# schematic_v1.net
KiCad netlist of a schematic drawn in EAGLE
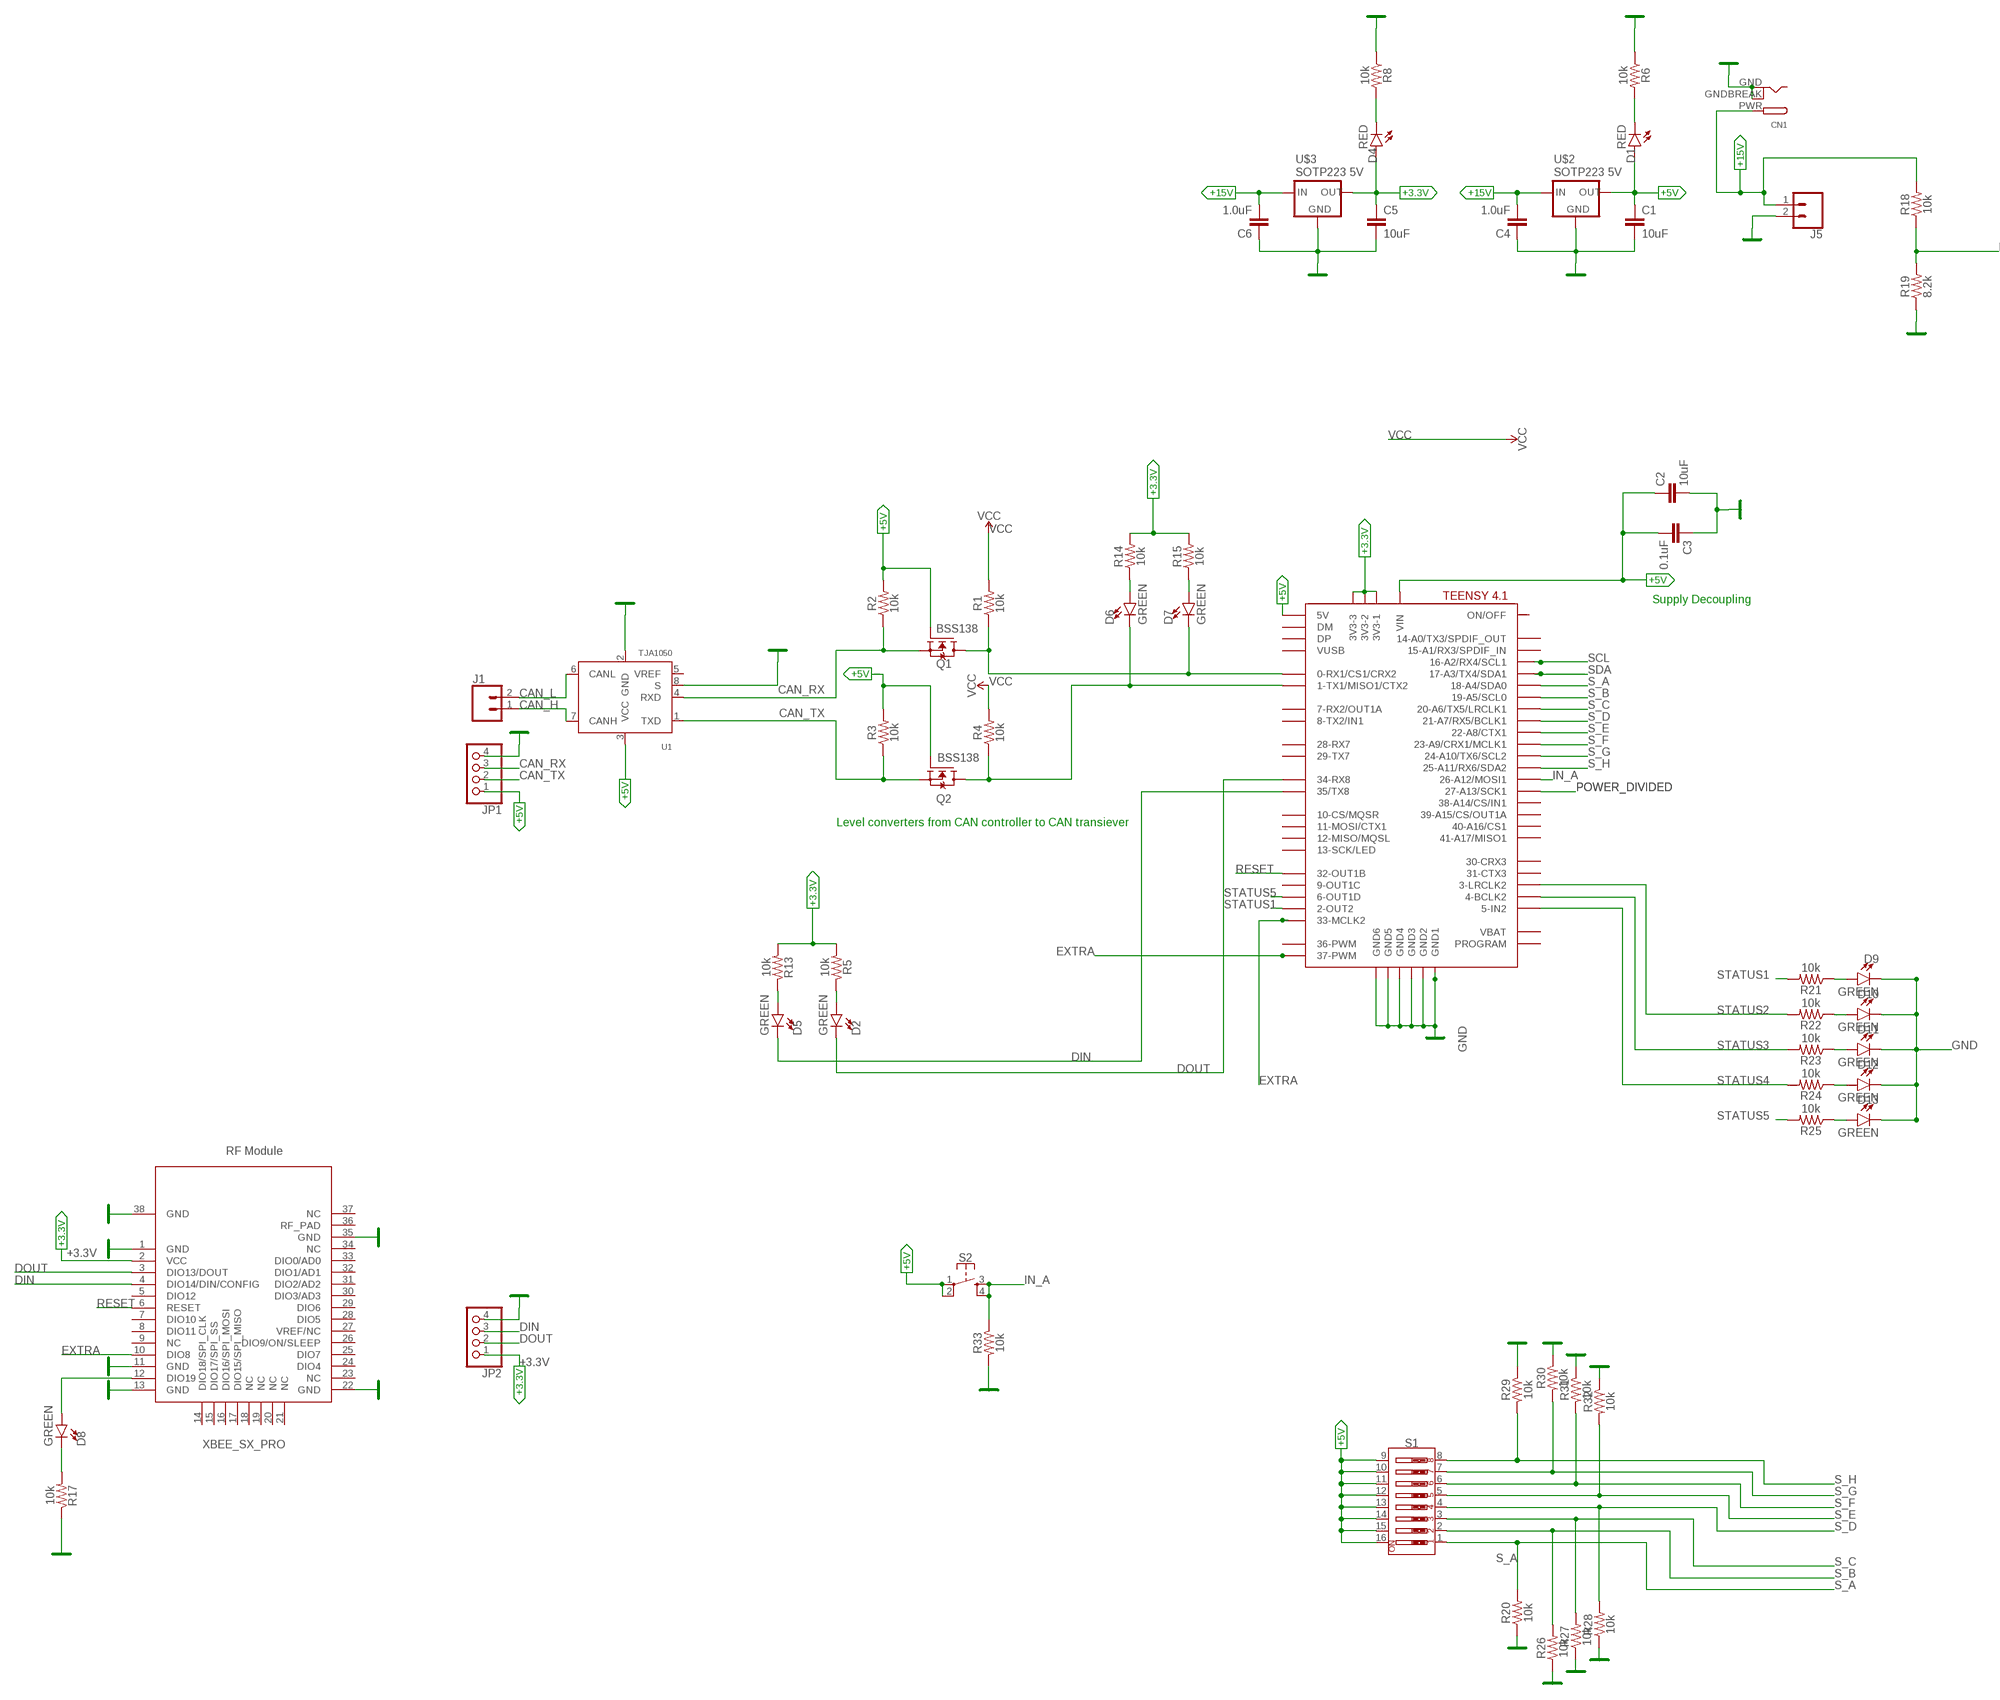
[diagram p0: schematic, sheet 1, part 1 of 2]
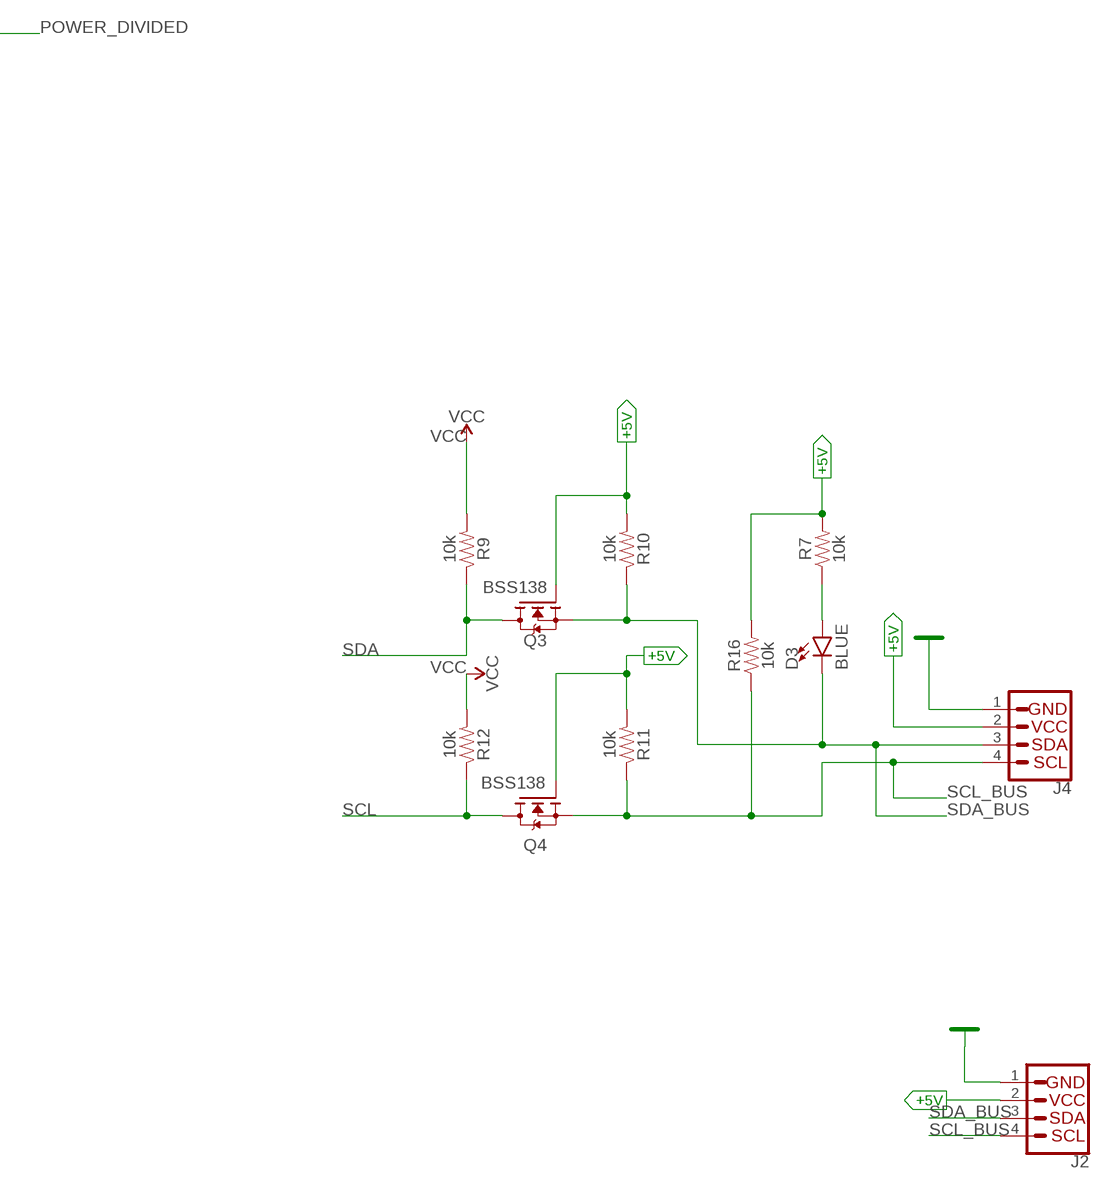
[diagram p1: schematic, sheet 1, part 2 of 2]

(export (version "E")
  (design (tool "Eeschema 10.0.6"))
  (components
    (comp (ref "C1")
      (value "10uF")
      (footprint "eagle-import:0603")
      (libsource (lib "eagle-import") (part "10UF-0603-6.3V-20%"))
    )
    (comp (ref "C2")
      (value "10uF")
      (footprint "eagle-import:0603")
      (libsource (lib "eagle-import") (part "10UF-0603-6.3V-20%"))
    )
    (comp (ref "C3")
      (value "0.1uF")
      (footprint "eagle-import:0603")
      (libsource (lib "eagle-import") (part "0.1UF-0603-25V-(+80/-20%)"))
    )
    (comp (ref "C4")
      (value "1.0uF")
      (footprint "eagle-import:0603")
      (libsource (lib "eagle-import") (part "1.0UF-0603-16V-10%"))
    )
    (comp (ref "C5")
      (value "10uF")
      (footprint "eagle-import:0603")
      (libsource (lib "eagle-import") (part "10UF-0603-6.3V-20%"))
    )
    (comp (ref "C6")
      (value "1.0uF")
      (footprint "eagle-import:0603")
      (libsource (lib "eagle-import") (part "1.0UF-0603-16V-10%"))
    )
    (comp (ref "CN1")
      (value "DCBARRELPTH")
      (footprint "eagle-import:DCJACK_2MM_PTH")
      (libsource (lib "eagle-import") (part "DCBARRELPTH"))
    )
    (comp (ref "D1")
      (value "RED")
      (footprint "eagle-import:LED-0603")
      (libsource (lib "eagle-import") (part "LED-RED0603"))
    )
    (comp (ref "D2")
      (value "GREEN")
      (footprint "eagle-import:LED-0603")
      (libsource (lib "eagle-import") (part "LED-GREEN0603"))
    )
    (comp (ref "D3")
      (value "BLUE")
      (footprint "eagle-import:LED-0603")
      (libsource (lib "eagle-import") (part "LED-BLUE0603"))
    )
    (comp (ref "D4")
      (value "RED")
      (footprint "eagle-import:LED-0603")
      (libsource (lib "eagle-import") (part "LED-RED0603"))
    )
    (comp (ref "D5")
      (value "GREEN")
      (footprint "eagle-import:LED-0603")
      (libsource (lib "eagle-import") (part "LED-GREEN0603"))
    )
    (comp (ref "D6")
      (value "GREEN")
      (footprint "eagle-import:LED-0603")
      (libsource (lib "eagle-import") (part "LED-GREEN0603"))
    )
    (comp (ref "D7")
      (value "GREEN")
      (footprint "eagle-import:LED-0603")
      (libsource (lib "eagle-import") (part "LED-GREEN0603"))
    )
    (comp (ref "D8")
      (value "GREEN")
      (footprint "eagle-import:LED-0603")
      (libsource (lib "eagle-import") (part "LED-GREEN0603"))
    )
    (comp (ref "D9")
      (value "GREEN")
      (footprint "eagle-import:LED-0603")
      (libsource (lib "eagle-import") (part "LED-GREEN0603"))
    )
    (comp (ref "D10")
      (value "GREEN")
      (footprint "eagle-import:LED-0603")
      (libsource (lib "eagle-import") (part "LED-GREEN0603"))
    )
    (comp (ref "D11")
      (value "GREEN")
      (footprint "eagle-import:LED-0603")
      (libsource (lib "eagle-import") (part "LED-GREEN0603"))
    )
    (comp (ref "D12")
      (value "GREEN")
      (footprint "eagle-import:LED-0603")
      (libsource (lib "eagle-import") (part "LED-GREEN0603"))
    )
    (comp (ref "D13")
      (value "GREEN")
      (footprint "eagle-import:LED-0603")
      (libsource (lib "eagle-import") (part "LED-GREEN0603"))
    )
    (comp (ref "J1")
      (value "CONN_02")
      (footprint "eagle-import:1X02")
      (libsource (lib "eagle-import") (part "CONN_02"))
    )
    (comp (ref "J2")
      (value "I2C_STANDARD")
      (footprint "eagle-import:1X04")
      (libsource (lib "eagle-import") (part "I2C_STANDARD"))
    )
    (comp (ref "J4")
      (value "I2C_STANDARD")
      (footprint "eagle-import:1X04")
      (libsource (lib "eagle-import") (part "I2C_STANDARD"))
    )
    (comp (ref "J5")
      (value "CONN_02LOCK_LONGPADS")
      (footprint "eagle-import:1X02_LOCK_LONGPADS")
      (libsource (lib "eagle-import") (part "CONN_02LOCK_LONGPADS"))
    )
    (comp (ref "JP1")
      (value "PINHD-1X4")
      (footprint "eagle-import:1X04")
      (libsource (lib "eagle-import") (part "PINHD-1X4"))
    )
    (comp (ref "JP2")
      (value "PINHD-1X4")
      (footprint "eagle-import:1X04")
      (libsource (lib "eagle-import") (part "PINHD-1X4"))
    )
    (comp (ref "Q1")
      (value "BSS138")
      (footprint "eagle-import:SOT95P240X111-3N")
      (fields (field (name "MF") "ON Semiconductor"))
      (libsource (lib "eagle-import") (part "BSS138"))
    )
    (comp (ref "Q2")
      (value "BSS138")
      (footprint "eagle-import:SOT95P240X111-3N")
      (fields (field (name "MF") "ON Semiconductor"))
      (libsource (lib "eagle-import") (part "BSS138"))
    )
    (comp (ref "Q3")
      (value "BSS138")
      (footprint "eagle-import:SOT95P240X111-3N")
      (fields (field (name "MF") "ON Semiconductor") (field (name "SPICEPREFIX") "Q"))
      (libsource (lib "eagle-import") (part "BSS138"))
    )
    (comp (ref "Q4")
      (value "BSS138")
      (footprint "eagle-import:SOT95P240X111-3N")
      (fields (field (name "MF") "ON Semiconductor") (field (name "SPICEPREFIX") "Q"))
      (libsource (lib "eagle-import") (part "BSS138"))
    )
    (comp (ref "R1")
      (value "10k")
      (footprint "eagle-import:0603")
      (libsource (lib "eagle-import") (part "10KOHM-0603-1/10W-1%"))
    )
    (comp (ref "R2")
      (value "10k")
      (footprint "eagle-import:0603")
      (libsource (lib "eagle-import") (part "10KOHM-0603-1/10W-1%"))
    )
    (comp (ref "R3")
      (value "10k")
      (footprint "eagle-import:0603")
      (libsource (lib "eagle-import") (part "10KOHM-0603-1/10W-1%"))
    )
    (comp (ref "R4")
      (value "10k")
      (footprint "eagle-import:0603")
      (libsource (lib "eagle-import") (part "10KOHM-0603-1/10W-1%"))
    )
    (comp (ref "R5")
      (value "10k")
      (footprint "eagle-import:0603")
      (libsource (lib "eagle-import") (part "10KOHM-0603-1/10W-1%"))
    )
    (comp (ref "R6")
      (value "10k")
      (footprint "eagle-import:0603")
      (libsource (lib "eagle-import") (part "10KOHM-0603-1/10W-1%"))
    )
    (comp (ref "R7")
      (value "10k")
      (footprint "eagle-import:0603")
      (libsource (lib "eagle-import") (part "10KOHM-0603-1/10W-1%"))
    )
    (comp (ref "R8")
      (value "10k")
      (footprint "eagle-import:0603")
      (libsource (lib "eagle-import") (part "10KOHM-0603-1/10W-1%"))
    )
    (comp (ref "R9")
      (value "10k")
      (footprint "eagle-import:0603")
      (fields (field (name "SPICEPREFIX") "R"))
      (libsource (lib "eagle-import") (part "10KOHM-0603-1/10W-1%"))
    )
    (comp (ref "R10")
      (value "10k")
      (footprint "eagle-import:0603")
      (fields (field (name "SPICEPREFIX") "R"))
      (libsource (lib "eagle-import") (part "10KOHM-0603-1/10W-1%"))
    )
    (comp (ref "R11")
      (value "10k")
      (footprint "eagle-import:0603")
      (fields (field (name "SPICEPREFIX") "R"))
      (libsource (lib "eagle-import") (part "10KOHM-0603-1/10W-1%"))
    )
    (comp (ref "R12")
      (value "10k")
      (footprint "eagle-import:0603")
      (fields (field (name "SPICEPREFIX") "R"))
      (libsource (lib "eagle-import") (part "10KOHM-0603-1/10W-1%"))
    )
    (comp (ref "R13")
      (value "10k")
      (footprint "eagle-import:0603")
      (libsource (lib "eagle-import") (part "10KOHM-0603-1/10W-1%"))
    )
    (comp (ref "R14")
      (value "10k")
      (footprint "eagle-import:0603")
      (libsource (lib "eagle-import") (part "10KOHM-0603-1/10W-1%"))
    )
    (comp (ref "R15")
      (value "10k")
      (footprint "eagle-import:0603")
      (libsource (lib "eagle-import") (part "10KOHM-0603-1/10W-1%"))
    )
    (comp (ref "R16")
      (value "10k")
      (footprint "eagle-import:0603")
      (libsource (lib "eagle-import") (part "10KOHM-0603-1/10W-1%"))
    )
    (comp (ref "R17")
      (value "10k")
      (footprint "eagle-import:0603")
      (libsource (lib "eagle-import") (part "10KOHM-0603-1/10W-1%"))
    )
    (comp (ref "R18")
      (value "10k")
      (footprint "eagle-import:0603")
      (libsource (lib "eagle-import") (part "10KOHM-0603-1/10W-1%"))
    )
    (comp (ref "R19")
      (value "8.2k")
      (footprint "eagle-import:0603")
      (libsource (lib "eagle-import") (part "8.2KOHM-0603-1/10W-5%"))
    )
    (comp (ref "R20")
      (value "10k")
      (footprint "eagle-import:0603")
      (libsource (lib "eagle-import") (part "10KOHM-0603-1/10W-1%"))
    )
    (comp (ref "R21")
      (value "10k")
      (footprint "eagle-import:0603")
      (libsource (lib "eagle-import") (part "10KOHM-0603-1/10W-1%"))
    )
    (comp (ref "R22")
      (value "10k")
      (footprint "eagle-import:0603")
      (libsource (lib "eagle-import") (part "10KOHM-0603-1/10W-1%"))
    )
    (comp (ref "R23")
      (value "10k")
      (footprint "eagle-import:0603")
      (libsource (lib "eagle-import") (part "10KOHM-0603-1/10W-1%"))
    )
    (comp (ref "R24")
      (value "10k")
      (footprint "eagle-import:0603")
      (libsource (lib "eagle-import") (part "10KOHM-0603-1/10W-1%"))
    )
    (comp (ref "R25")
      (value "10k")
      (footprint "eagle-import:0603")
      (libsource (lib "eagle-import") (part "10KOHM-0603-1/10W-1%"))
    )
    (comp (ref "R26")
      (value "10k")
      (footprint "eagle-import:0603")
      (libsource (lib "eagle-import") (part "10KOHM-0603-1/10W-1%"))
    )
    (comp (ref "R27")
      (value "10k")
      (footprint "eagle-import:0603")
      (libsource (lib "eagle-import") (part "10KOHM-0603-1/10W-1%"))
    )
    (comp (ref "R28")
      (value "10k")
      (footprint "eagle-import:0603")
      (libsource (lib "eagle-import") (part "10KOHM-0603-1/10W-1%"))
    )
    (comp (ref "R29")
      (value "10k")
      (footprint "eagle-import:0603")
      (libsource (lib "eagle-import") (part "10KOHM-0603-1/10W-1%"))
    )
    (comp (ref "R30")
      (value "10k")
      (footprint "eagle-import:0603")
      (libsource (lib "eagle-import") (part "10KOHM-0603-1/10W-1%"))
    )
    (comp (ref "R31")
      (value "10k")
      (footprint "eagle-import:0603")
      (libsource (lib "eagle-import") (part "10KOHM-0603-1/10W-1%"))
    )
    (comp (ref "R32")
      (value "10k")
      (footprint "eagle-import:0603")
      (libsource (lib "eagle-import") (part "10KOHM-0603-1/10W-1%"))
    )
    (comp (ref "R33")
      (value "10k")
      (footprint "eagle-import:0603")
      (libsource (lib "eagle-import") (part "10KOHM-0603-1/10W-1%"))
    )
    (comp (ref "S1")
      (value "DIP-08-PTH")
      (footprint "eagle-import:DIPSWITCH-08")
      (libsource (lib "eagle-import") (part "DIP-08-PTH"))
    )
    (comp (ref "S2")
      (value "MOMENTARY-SWITCH-SPST-2-SMD-5.2MM")
      (footprint "eagle-import:TACTILE_SWITCH_SMD_5.2MM")
      (libsource (lib "eagle-import") (part "MOMENTARY-SWITCH-SPST-2-SMD-5.2MM"))
    )
    (comp (ref "U$1")
      (value "XBEE_SX_PRO")
      (footprint "eagle-import:XBEE_SX_PRO")
      (libsource (lib "eagle-import") (part "XBEE_SX_PRO"))
    )
    (comp (ref "U$2")
      (value "SOTP223 5V")
      (footprint "eagle-import:SOT223")
      (libsource (lib "eagle-import") (part "V_REG_LD1117VXXLD1117-SMD"))
    )
    (comp (ref "U$3")
      (value "SOTP223 5V")
      (footprint "eagle-import:SOT223")
      (libsource (lib "eagle-import") (part "V_REG_LD1117VXXLD1117-SMD"))
    )
    (comp (ref "U$4")
      (value "TEENSY41-E")
      (footprint "eagle-import:TENNSY41-E")
      (libsource (lib "eagle-import") (part "TEENSY41-E"))
    )
    (comp (ref "U1")
      (value "TJA1050")
      (footprint "eagle-import:SOT96-1")
      (fields (field (name "MF") "NXP USA"))
      (libsource (lib "eagle-import") (part "TJA1050"))
    )
  )
  (nets
    (net (code "1") (name "+3.3V") (class "Default")
      (node (ref "C5") (pin "1") (pinfunction "1_1") (pintype "passive"))
      (node (ref "D4") (pin "A") (pinfunction "A_A") (pintype "passive"))
      (node (ref "JP2") (pin "1") (pinfunction "1_1") (pintype "passive"))
      (node (ref "R13") (pin "2") (pinfunction "2_2") (pintype "passive"))
      (node (ref "R14") (pin "2") (pinfunction "2_2") (pintype "passive"))
      (node (ref "R15") (pin "2") (pinfunction "2_2") (pintype "passive"))
      (node (ref "R5") (pin "2") (pinfunction "2_2") (pintype "passive"))
      (node (ref "U$1") (pin "2") (pinfunction "VCC_2") (pintype "power_in"))
      (node (ref "U$3") (pin "2") (pinfunction "OUT_2") (pintype "passive"))
      (node (ref "U$4") (pin "3V3-1") (pinfunction "3V3-1_3V3-1") (pintype "bidirectional"))
      (node (ref "U$4") (pin "3V3-2") (pinfunction "3V3-2_3V3-2") (pintype "bidirectional"))
      (node (ref "U$4") (pin "3V3-3") (pinfunction "3V3-3_3V3-3") (pintype "bidirectional"))
    )
    (net (code "2") (name "+5V") (class "Default")
      (node (ref "C1") (pin "1") (pinfunction "1_1") (pintype "passive"))
      (node (ref "C2") (pin "1") (pinfunction "1_1") (pintype "passive"))
      (node (ref "C3") (pin "2") (pinfunction "2_2") (pintype "passive"))
      (node (ref "D1") (pin "A") (pinfunction "A_A") (pintype "passive"))
      (node (ref "J2") (pin "2") (pinfunction "2_2") (pintype "power_in"))
      (node (ref "J4") (pin "2") (pinfunction "2_2") (pintype "power_in"))
      (node (ref "JP1") (pin "1") (pinfunction "1_1") (pintype "passive"))
      (node (ref "Q1") (pin "1") (pinfunction "G_1") (pintype "passive"))
      (node (ref "Q2") (pin "1") (pinfunction "G_1") (pintype "passive"))
      (node (ref "Q3") (pin "1") (pinfunction "G_1") (pintype "passive"))
      (node (ref "Q4") (pin "1") (pinfunction "G_1") (pintype "passive"))
      (node (ref "R10") (pin "2") (pinfunction "2_2") (pintype "passive"))
      (node (ref "R11") (pin "2") (pinfunction "2_2") (pintype "passive"))
      (node (ref "R16") (pin "2") (pinfunction "2_2") (pintype "passive"))
      (node (ref "R2") (pin "2") (pinfunction "2_2") (pintype "passive"))
      (node (ref "R3") (pin "2") (pinfunction "2_2") (pintype "passive"))
      (node (ref "R7") (pin "2") (pinfunction "2_2") (pintype "passive"))
      (node (ref "S1") (pin "10") (pinfunction "10_10") (pintype "passive"))
      (node (ref "S1") (pin "11") (pinfunction "11_11") (pintype "passive"))
      (node (ref "S1") (pin "12") (pinfunction "12_12") (pintype "passive"))
      (node (ref "S1") (pin "13") (pinfunction "13_13") (pintype "passive"))
      (node (ref "S1") (pin "14") (pinfunction "14_14") (pintype "passive"))
      (node (ref "S1") (pin "15") (pinfunction "15_15") (pintype "passive"))
      (node (ref "S1") (pin "16") (pinfunction "16_16") (pintype "passive"))
      (node (ref "S1") (pin "9") (pinfunction "9_9") (pintype "passive"))
      (node (ref "S2") (pin "1") (pinfunction "1_1") (pintype "passive"))
      (node (ref "S2") (pin "2") (pinfunction "2_2") (pintype "passive"))
      (node (ref "U$2") (pin "2") (pinfunction "OUT_2") (pintype "passive"))
      (node (ref "U$4") (pin "+5V") (pinfunction "5V_+5V") (pintype "bidirectional"))
      (node (ref "U$4") (pin "VIN") (pinfunction "VIN_VIN") (pintype "bidirectional"))
      (node (ref "U1") (pin "3") (pinfunction "VCC_3") (pintype "bidirectional"))
    )
    (net (code "3") (name "+15V") (class "Default")
      (node (ref "C4") (pin "2") (pinfunction "2_2") (pintype "passive"))
      (node (ref "C6") (pin "2") (pinfunction "2_2") (pintype "passive"))
      (node (ref "CN1") (pin "PWR") (pinfunction "PWR_PWR") (pintype "power_in"))
      (node (ref "J5") (pin "1") (pinfunction "1_1") (pintype "passive"))
      (node (ref "R18") (pin "2") (pinfunction "2_2") (pintype "passive"))
      (node (ref "U$2") (pin "3") (pinfunction "IN_3") (pintype "input"))
      (node (ref "U$3") (pin "3") (pinfunction "IN_3") (pintype "input"))
    )
    (net (code "4") (name "/CAN_H") (class "Default")
      (node (ref "J1") (pin "1") (pinfunction "1_1") (pintype "passive"))
      (node (ref "U1") (pin "7") (pinfunction "CANH_7") (pintype "bidirectional"))
    )
    (net (code "5") (name "/CAN_L") (class "Default")
      (node (ref "J1") (pin "2") (pinfunction "2_2") (pintype "passive"))
      (node (ref "U1") (pin "6") (pinfunction "CANL_6") (pintype "bidirectional"))
    )
    (net (code "6") (name "/CAN_RX") (class "Default")
      (node (ref "JP1") (pin "3") (pinfunction "3_3") (pintype "passive"))
      (node (ref "Q1") (pin "2") (pinfunction "S_2") (pintype "passive"))
      (node (ref "R2") (pin "1") (pinfunction "1_1") (pintype "passive"))
      (node (ref "U1") (pin "4") (pinfunction "RXD_4") (pintype "bidirectional"))
    )
    (net (code "7") (name "/CAN_TX") (class "Default")
      (node (ref "JP1") (pin "2") (pinfunction "2_2") (pintype "passive"))
      (node (ref "Q2") (pin "2") (pinfunction "S_2") (pintype "passive"))
      (node (ref "R3") (pin "1") (pinfunction "1_1") (pintype "passive"))
      (node (ref "U1") (pin "1") (pinfunction "TXD_1") (pintype "output"))
    )
    (net (code "8") (name "/DIN") (class "Default")
      (node (ref "D5") (pin "C") (pinfunction "C_C") (pintype "passive"))
      (node (ref "JP2") (pin "3") (pinfunction "3_3") (pintype "passive"))
      (node (ref "U$1") (pin "4") (pinfunction "DIO14/DIN/CONFIG_4") (pintype "bidirectional"))
      (node (ref "U$4") (pin "35-TX8") (pinfunction "35/TX8_35-TX8") (pintype "bidirectional"))
    )
    (net (code "9") (name "/DOUT") (class "Default")
      (node (ref "D2") (pin "C") (pinfunction "C_C") (pintype "passive"))
      (node (ref "JP2") (pin "2") (pinfunction "2_2") (pintype "passive"))
      (node (ref "U$1") (pin "3") (pinfunction "DIO13/DOUT_3") (pintype "bidirectional"))
      (node (ref "U$4") (pin "34-RX8") (pinfunction "34-RX8_34-RX8") (pintype "bidirectional"))
    )
    (net (code "10") (name "/EXTRA") (class "Default")
      (node (ref "U$1") (pin "10") (pinfunction "DIO8_10") (pintype "bidirectional"))
      (node (ref "U$4") (pin "33-MCLK2") (pinfunction "33-MCLK2_33-MCLK2") (pintype "bidirectional"))
    )
    (net (code "11") (name "/IN_A") (class "Default")
      (node (ref "R33") (pin "1") (pinfunction "1_1") (pintype "passive"))
      (node (ref "S2") (pin "3") (pinfunction "3_3") (pintype "passive"))
      (node (ref "S2") (pin "4") (pinfunction "4_4") (pintype "passive"))
      (node (ref "U$4") (pin "26-A12/MOSI1") (pinfunction "26-A12/MOSI1_26-A12/MOSI1") (pintype "bidirectional"))
    )
    (net (code "12") (name "/POWER_DIVIDED") (class "Default")
      (node (ref "R18") (pin "1") (pinfunction "1_1") (pintype "passive"))
      (node (ref "R19") (pin "2") (pinfunction "2_2") (pintype "passive"))
      (node (ref "U$4") (pin "27-A13/SCK1") (pinfunction "27-A13/SCK1_27-A13/SCK1") (pintype "bidirectional"))
    )
    (net (code "13") (name "/RESET") (class "Default")
      (node (ref "U$1") (pin "6") (pinfunction "RESET_6") (pintype "bidirectional"))
      (node (ref "U$4") (pin "32-OUT1B") (pinfunction "32-OUT1B_32-OUT1B") (pintype "bidirectional"))
    )
    (net (code "14") (name "/SCL") (class "Default")
      (node (ref "Q4") (pin "3") (pinfunction "D_3") (pintype "passive"))
      (node (ref "R12") (pin "1") (pinfunction "1_1") (pintype "passive"))
      (node (ref "U$4") (pin "16-A2/RX4/SCL1") (pinfunction "16-A2/RX4/SCL1_16-A2/RX4/SCL1") (pintype "bidirectional"))
    )
    (net (code "15") (name "/SCL_BUS") (class "Default")
      (node (ref "J2") (pin "4") (pinfunction "4_4") (pintype "passive"))
      (node (ref "J4") (pin "4") (pinfunction "4_4") (pintype "passive"))
      (node (ref "Q4") (pin "2") (pinfunction "S_2") (pintype "passive"))
      (node (ref "R11") (pin "1") (pinfunction "1_1") (pintype "passive"))
      (node (ref "R16") (pin "1") (pinfunction "1_1") (pintype "passive"))
    )
    (net (code "16") (name "/SDA") (class "Default")
      (node (ref "Q3") (pin "3") (pinfunction "D_3") (pintype "passive"))
      (node (ref "R9") (pin "1") (pinfunction "1_1") (pintype "passive"))
      (node (ref "U$4") (pin "17-A3/TX4/SDA1") (pinfunction "17-A3/TX4/SDA1_17-A3/TX4/SDA1") (pintype "bidirectional"))
    )
    (net (code "17") (name "/SDA_BUS") (class "Default")
      (node (ref "D3") (pin "C") (pinfunction "C_C") (pintype "passive"))
      (node (ref "J2") (pin "3") (pinfunction "3_3") (pintype "passive"))
      (node (ref "J4") (pin "3") (pinfunction "3_3") (pintype "passive"))
      (node (ref "Q3") (pin "2") (pinfunction "S_2") (pintype "passive"))
      (node (ref "R10") (pin "1") (pinfunction "1_1") (pintype "passive"))
    )
    (net (code "18") (name "/STATUS1") (class "Default")
      (node (ref "R21") (pin "2") (pinfunction "2_2") (pintype "passive"))
      (node (ref "U$4") (pin "2-OUT2") (pinfunction "2-OUT2_2-OUT2") (pintype "bidirectional"))
    )
    (net (code "19") (name "/STATUS2") (class "Default")
      (node (ref "R22") (pin "2") (pinfunction "2_2") (pintype "passive"))
      (node (ref "U$4") (pin "3-LRCLK2") (pinfunction "3-LRCLK2_3-LRCLK2") (pintype "bidirectional"))
    )
    (net (code "20") (name "/STATUS3") (class "Default")
      (node (ref "R23") (pin "2") (pinfunction "2_2") (pintype "passive"))
      (node (ref "U$4") (pin "4-BCLK2") (pinfunction "4-BCLK2_4-BCLK2") (pintype "bidirectional"))
    )
    (net (code "21") (name "/STATUS4") (class "Default")
      (node (ref "R24") (pin "2") (pinfunction "2_2") (pintype "passive"))
      (node (ref "U$4") (pin "5-IN2") (pinfunction "5-IN2_5-IN2") (pintype "bidirectional"))
    )
    (net (code "22") (name "/STATUS5") (class "Default")
      (node (ref "R25") (pin "2") (pinfunction "2_2") (pintype "passive"))
      (node (ref "U$4") (pin "6-OUT1D") (pinfunction "6-OUT1D_6-OUT1D") (pintype "bidirectional"))
    )
    (net (code "23") (name "/S_A") (class "Default")
      (node (ref "R20") (pin "2") (pinfunction "2_2") (pintype "passive"))
      (node (ref "S1") (pin "1") (pinfunction "1_1") (pintype "passive"))
      (node (ref "U$4") (pin "18-A4/SDA0") (pinfunction "18-A4/SDA0_18-A4/SDA0") (pintype "bidirectional"))
    )
    (net (code "24") (name "/S_B") (class "Default")
      (node (ref "R26") (pin "2") (pinfunction "2_2") (pintype "passive"))
      (node (ref "S1") (pin "2") (pinfunction "2_2") (pintype "passive"))
      (node (ref "U$4") (pin "19-A5/SCL0") (pinfunction "19-A5/SCL0_19-A5/SCL0") (pintype "bidirectional"))
    )
    (net (code "25") (name "/S_C") (class "Default")
      (node (ref "R27") (pin "2") (pinfunction "2_2") (pintype "passive"))
      (node (ref "S1") (pin "3") (pinfunction "3_3") (pintype "passive"))
      (node (ref "U$4") (pin "20-A6/TX5/LRCLK1") (pinfunction "20-A6/TX5/LRCLK1_20-A6/TX5/LRCLK1") (pintype "bidirectional"))
    )
    (net (code "26") (name "/S_D") (class "Default")
      (node (ref "R28") (pin "2") (pinfunction "2_2") (pintype "passive"))
      (node (ref "S1") (pin "4") (pinfunction "4_4") (pintype "passive"))
      (node (ref "U$4") (pin "21-A7/RX5/BCLK1") (pinfunction "21-A7/RX5/BCLK1_21-A7/RX5/BCLK1") (pintype "bidirectional"))
    )
    (net (code "27") (name "/S_E") (class "Default")
      (node (ref "R32") (pin "2") (pinfunction "2_2") (pintype "passive"))
      (node (ref "S1") (pin "5") (pinfunction "5_5") (pintype "passive"))
      (node (ref "U$4") (pin "22-A8/CTX1") (pinfunction "22-A8/CTX1_22-A8/CTX1") (pintype "bidirectional"))
    )
    (net (code "28") (name "/S_F") (class "Default")
      (node (ref "R31") (pin "2") (pinfunction "2_2") (pintype "passive"))
      (node (ref "S1") (pin "6") (pinfunction "6_6") (pintype "passive"))
      (node (ref "U$4") (pin "23-A9/CRX1/MCLK1") (pinfunction "23-A9/CRX1/MCLK1_23-A9/CRX1/MCLK1") (pintype "bidirectional"))
    )
    (net (code "29") (name "/S_G") (class "Default")
      (node (ref "R30") (pin "2") (pinfunction "2_2") (pintype "passive"))
      (node (ref "S1") (pin "7") (pinfunction "7_7") (pintype "passive"))
      (node (ref "U$4") (pin "24-A10/TX6/SCL2") (pinfunction "24-A10/TX6/SCL2_24-A10/TX6/SCL2") (pintype "bidirectional"))
    )
    (net (code "30") (name "/S_H") (class "Default")
      (node (ref "R29") (pin "2") (pinfunction "2_2") (pintype "passive"))
      (node (ref "S1") (pin "8") (pinfunction "8_8") (pintype "passive"))
      (node (ref "U$4") (pin "25-A11/RX6/SDA2") (pinfunction "25-A11/RX6/SDA2_25-A11/RX6/SDA2") (pintype "bidirectional"))
    )
    (net (code "31") (name "GND") (class "Default")
      (node (ref "C1") (pin "2") (pinfunction "2_2") (pintype "passive"))
      (node (ref "C2") (pin "2") (pinfunction "2_2") (pintype "passive"))
      (node (ref "C3") (pin "1") (pinfunction "1_1") (pintype "passive"))
      (node (ref "C4") (pin "1") (pinfunction "1_1") (pintype "passive"))
      (node (ref "C5") (pin "2") (pinfunction "2_2") (pintype "passive"))
      (node (ref "C6") (pin "1") (pinfunction "1_1") (pintype "passive"))
      (node (ref "CN1") (pin "GND") (pinfunction "GND_GND") (pintype "power_in"))
      (node (ref "CN1") (pin "GNDBREAK") (pinfunction "GNDBREAK_GNDBREAK") (pintype "power_in"))
      (node (ref "D10") (pin "C") (pinfunction "C_C") (pintype "passive"))
      (node (ref "D11") (pin "C") (pinfunction "C_C") (pintype "passive"))
      (node (ref "D12") (pin "C") (pinfunction "C_C") (pintype "passive"))
      (node (ref "D13") (pin "C") (pinfunction "C_C") (pintype "passive"))
      (node (ref "D9") (pin "C") (pinfunction "C_C") (pintype "passive"))
      (node (ref "J2") (pin "1") (pinfunction "1_1") (pintype "power_in"))
      (node (ref "J4") (pin "1") (pinfunction "1_1") (pintype "power_in"))
      (node (ref "J5") (pin "2") (pinfunction "2_2") (pintype "passive"))
      (node (ref "JP1") (pin "4") (pinfunction "4_4") (pintype "passive"))
      (node (ref "JP2") (pin "4") (pinfunction "4_4") (pintype "passive"))
      (node (ref "R17") (pin "1") (pinfunction "1_1") (pintype "passive"))
      (node (ref "R19") (pin "1") (pinfunction "1_1") (pintype "passive"))
      (node (ref "R20") (pin "1") (pinfunction "1_1") (pintype "passive"))
      (node (ref "R26") (pin "1") (pinfunction "1_1") (pintype "passive"))
      (node (ref "R27") (pin "1") (pinfunction "1_1") (pintype "passive"))
      (node (ref "R28") (pin "1") (pinfunction "1_1") (pintype "passive"))
      (node (ref "R29") (pin "1") (pinfunction "1_1") (pintype "passive"))
      (node (ref "R30") (pin "1") (pinfunction "1_1") (pintype "passive"))
      (node (ref "R31") (pin "1") (pinfunction "1_1") (pintype "passive"))
      (node (ref "R32") (pin "1") (pinfunction "1_1") (pintype "passive"))
      (node (ref "R33") (pin "2") (pinfunction "2_2") (pintype "passive"))
      (node (ref "R6") (pin "1") (pinfunction "1_1") (pintype "passive"))
      (node (ref "R8") (pin "1") (pinfunction "1_1") (pintype "passive"))
      (node (ref "U$1") (pin "1") (pinfunction "GND_1") (pintype "bidirectional"))
      (node (ref "U$1") (pin "11") (pinfunction "GND_11") (pintype "bidirectional"))
      (node (ref "U$1") (pin "13") (pinfunction "GND_13") (pintype "power_in"))
      (node (ref "U$1") (pin "22") (pinfunction "GND_22") (pintype "power_in"))
      (node (ref "U$1") (pin "35") (pinfunction "GND_35") (pintype "power_in"))
      (node (ref "U$1") (pin "38") (pinfunction "GND_38") (pintype "power_in"))
      (node (ref "U$2") (pin "1") (pinfunction "GND_1") (pintype "input"))
      (node (ref "U$3") (pin "1") (pinfunction "GND_1") (pintype "input"))
      (node (ref "U$4") (pin "GND1") (pinfunction "GND1_GND1") (pintype "bidirectional"))
      (node (ref "U$4") (pin "GND2") (pinfunction "GND2_GND2") (pintype "bidirectional"))
      (node (ref "U$4") (pin "GND3") (pinfunction "GND3_GND3") (pintype "bidirectional"))
      (node (ref "U$4") (pin "GND4") (pinfunction "GND4_GND4") (pintype "bidirectional"))
      (node (ref "U$4") (pin "GND5") (pinfunction "GND5_GND5") (pintype "bidirectional"))
      (node (ref "U$4") (pin "GND6") (pinfunction "GND6_GND6") (pintype "bidirectional"))
      (node (ref "U1") (pin "2") (pinfunction "GND_2") (pintype "bidirectional"))
      (node (ref "U1") (pin "8") (pinfunction "S_8") (pintype "power_in"))
    )
    (net (code "32") (name "Net-(D1-PadC)") (class "Default")
      (node (ref "D1") (pin "C") (pinfunction "C_C") (pintype "passive"))
      (node (ref "R6") (pin "2") (pinfunction "2_2") (pintype "passive"))
    )
    (net (code "33") (name "Net-(D2-PadA)") (class "Default")
      (node (ref "D2") (pin "A") (pinfunction "A_A") (pintype "passive"))
      (node (ref "R5") (pin "1") (pinfunction "1_1") (pintype "passive"))
    )
    (net (code "34") (name "Net-(D3-PadA)") (class "Default")
      (node (ref "D3") (pin "A") (pinfunction "A_A") (pintype "passive"))
      (node (ref "R7") (pin "1") (pinfunction "1_1") (pintype "passive"))
    )
    (net (code "35") (name "Net-(D4-PadC)") (class "Default")
      (node (ref "D4") (pin "C") (pinfunction "C_C") (pintype "passive"))
      (node (ref "R8") (pin "2") (pinfunction "2_2") (pintype "passive"))
    )
    (net (code "36") (name "Net-(D5-PadA)") (class "Default")
      (node (ref "D5") (pin "A") (pinfunction "A_A") (pintype "passive"))
      (node (ref "R13") (pin "1") (pinfunction "1_1") (pintype "passive"))
    )
    (net (code "37") (name "Net-(D6-PadA)") (class "Default")
      (node (ref "D6") (pin "A") (pinfunction "A_A") (pintype "passive"))
      (node (ref "R14") (pin "1") (pinfunction "1_1") (pintype "passive"))
    )
    (net (code "38") (name "Net-(D7-PadA)") (class "Default")
      (node (ref "D7") (pin "A") (pinfunction "A_A") (pintype "passive"))
      (node (ref "R15") (pin "1") (pinfunction "1_1") (pintype "passive"))
    )
    (net (code "39") (name "Net-(D8-PadC)") (class "Default")
      (node (ref "D8") (pin "C") (pinfunction "C_C") (pintype "passive"))
      (node (ref "R17") (pin "2") (pinfunction "2_2") (pintype "passive"))
    )
    (net (code "40") (name "Net-(D9-PadA)") (class "Default")
      (node (ref "D9") (pin "A") (pinfunction "A_A") (pintype "passive"))
      (node (ref "R21") (pin "1") (pinfunction "1_1") (pintype "passive"))
    )
    (net (code "41") (name "Net-(D10-PadA)") (class "Default")
      (node (ref "D10") (pin "A") (pinfunction "A_A") (pintype "passive"))
      (node (ref "R22") (pin "1") (pinfunction "1_1") (pintype "passive"))
    )
    (net (code "42") (name "Net-(D11-PadA)") (class "Default")
      (node (ref "D11") (pin "A") (pinfunction "A_A") (pintype "passive"))
      (node (ref "R23") (pin "1") (pinfunction "1_1") (pintype "passive"))
    )
    (net (code "43") (name "Net-(D12-PadA)") (class "Default")
      (node (ref "D12") (pin "A") (pinfunction "A_A") (pintype "passive"))
      (node (ref "R24") (pin "1") (pinfunction "1_1") (pintype "passive"))
    )
    (net (code "44") (name "Net-(D13-PadA)") (class "Default")
      (node (ref "D13") (pin "A") (pinfunction "A_A") (pintype "passive"))
      (node (ref "R25") (pin "1") (pinfunction "1_1") (pintype "passive"))
    )
    (net (code "45") (name "Net-(Q1-D)") (class "Default")
      (node (ref "D7") (pin "C") (pinfunction "C_C") (pintype "passive"))
      (node (ref "Q1") (pin "3") (pinfunction "D_3") (pintype "passive"))
      (node (ref "R1") (pin "1") (pinfunction "1_1") (pintype "passive"))
      (node (ref "U$4") (pin "0-RX1/CS1/CRX2") (pinfunction "0-RX1/CS1/CRX2_0-RX1/CS1/CRX2") (pintype "bidirectional"))
    )
    (net (code "46") (name "Net-(Q2-D)") (class "Default")
      (node (ref "D6") (pin "C") (pinfunction "C_C") (pintype "passive"))
      (node (ref "Q2") (pin "3") (pinfunction "D_3") (pintype "passive"))
      (node (ref "R4") (pin "1") (pinfunction "1_1") (pintype "passive"))
      (node (ref "U$4") (pin "1-TX1/MISO1/CTX2") (pinfunction "1-TX1/MISO1/CTX2_1-TX1/MISO1/CTX2") (pintype "bidirectional"))
    )
    (net (code "47") (name "Net-(U$1-DIO19)") (class "Default")
      (node (ref "D8") (pin "A") (pinfunction "A_A") (pintype "passive"))
      (node (ref "U$1") (pin "12") (pinfunction "DIO19_12") (pintype "bidirectional"))
    )
    (net (code "48") (name "VCC") (class "Default")
      (node (ref "R1") (pin "2") (pinfunction "2_2") (pintype "passive"))
      (node (ref "R12") (pin "2") (pinfunction "2_2") (pintype "passive"))
      (node (ref "R4") (pin "2") (pinfunction "2_2") (pintype "passive"))
      (node (ref "R9") (pin "2") (pinfunction "2_2") (pintype "passive"))
    )
    (net (code "49") (name "unconnected-(U$1-DIO0{slash}AD0-Pad33)") (class "Default")
      (node (ref "U$1") (pin "33") (pinfunction "DIO0/AD0_33") (pintype "bidirectional"))
    )
    (net (code "50") (name "unconnected-(U$1-DIO1{slash}AD1-Pad32)") (class "Default")
      (node (ref "U$1") (pin "32") (pinfunction "DIO1/AD1_32") (pintype "bidirectional"))
    )
    (net (code "51") (name "unconnected-(U$1-DIO2{slash}AD2-Pad31)") (class "Default")
      (node (ref "U$1") (pin "31") (pinfunction "DIO2/AD2_31") (pintype "bidirectional"))
    )
    (net (code "52") (name "unconnected-(U$1-DIO3{slash}AD3-Pad30)") (class "Default")
      (node (ref "U$1") (pin "30") (pinfunction "DIO3/AD3_30") (pintype "bidirectional"))
    )
    (net (code "53") (name "unconnected-(U$1-DIO4-Pad24)") (class "Default")
      (node (ref "U$1") (pin "24") (pinfunction "DIO4_24") (pintype "bidirectional"))
    )
    (net (code "54") (name "unconnected-(U$1-DIO5-Pad28)") (class "Default")
      (node (ref "U$1") (pin "28") (pinfunction "DIO5_28") (pintype "bidirectional"))
    )
    (net (code "55") (name "unconnected-(U$1-DIO6-Pad29)") (class "Default")
      (node (ref "U$1") (pin "29") (pinfunction "DIO6_29") (pintype "bidirectional"))
    )
    (net (code "56") (name "unconnected-(U$1-DIO7-Pad25)") (class "Default")
      (node (ref "U$1") (pin "25") (pinfunction "DIO7_25") (pintype "bidirectional"))
    )
    (net (code "57") (name "unconnected-(U$1-DIO9{slash}ON{slash}SLEEP-Pad26)") (class "Default")
      (node (ref "U$1") (pin "26") (pinfunction "DIO9/ON/SLEEP_26") (pintype "bidirectional"))
    )
    (net (code "58") (name "unconnected-(U$1-DIO10-Pad7)") (class "Default")
      (node (ref "U$1") (pin "7") (pinfunction "DIO10_7") (pintype "bidirectional"))
    )
    (net (code "59") (name "unconnected-(U$1-DIO11-Pad8)") (class "Default")
      (node (ref "U$1") (pin "8") (pinfunction "DIO11_8") (pintype "bidirectional"))
    )
    (net (code "60") (name "unconnected-(U$1-DIO12-Pad5)") (class "Default")
      (node (ref "U$1") (pin "5") (pinfunction "DIO12_5") (pintype "bidirectional"))
    )
    (net (code "61") (name "unconnected-(U$1-DIO15{slash}SPI_MISO-Pad17)") (class "Default")
      (node (ref "U$1") (pin "17") (pinfunction "DIO15/SPI_MISO_17") (pintype "bidirectional"))
    )
    (net (code "62") (name "unconnected-(U$1-DIO16{slash}SPI_MOSI-Pad16)") (class "Default")
      (node (ref "U$1") (pin "16") (pinfunction "DIO16/SPI_MOSI_16") (pintype "bidirectional"))
    )
    (net (code "63") (name "unconnected-(U$1-DIO17{slash}SPI_SS-Pad15)") (class "Default")
      (node (ref "U$1") (pin "15") (pinfunction "DIO17/SPI_SS_15") (pintype "bidirectional"))
    )
    (net (code "64") (name "unconnected-(U$1-DIO18{slash}SPI_CLK-Pad14)") (class "Default")
      (node (ref "U$1") (pin "14") (pinfunction "DIO18/SPI_CLK_14") (pintype "bidirectional"))
    )
    (net (code "65") (name "unconnected-(U$1-NC-Pad9)") (class "Default")
      (node (ref "U$1") (pin "9") (pinfunction "NC_9") (pintype "no_connect"))
    )
    (net (code "66") (name "unconnected-(U$1-NC-Pad18)") (class "Default")
      (node (ref "U$1") (pin "18") (pinfunction "NC_18") (pintype "no_connect"))
    )
    (net (code "67") (name "unconnected-(U$1-NC-Pad19)") (class "Default")
      (node (ref "U$1") (pin "19") (pinfunction "NC_19") (pintype "no_connect"))
    )
    (net (code "68") (name "unconnected-(U$1-NC-Pad20)") (class "Default")
      (node (ref "U$1") (pin "20") (pinfunction "NC_20") (pintype "no_connect"))
    )
    (net (code "69") (name "unconnected-(U$1-NC-Pad21)") (class "Default")
      (node (ref "U$1") (pin "21") (pinfunction "NC_21") (pintype "no_connect"))
    )
    (net (code "70") (name "unconnected-(U$1-NC-Pad23)") (class "Default")
      (node (ref "U$1") (pin "23") (pinfunction "NC_23") (pintype "no_connect"))
    )
    (net (code "71") (name "unconnected-(U$1-NC-Pad34)") (class "Default")
      (node (ref "U$1") (pin "34") (pinfunction "NC_34") (pintype "no_connect"))
    )
    (net (code "72") (name "unconnected-(U$1-NC-Pad37)") (class "Default")
      (node (ref "U$1") (pin "37") (pinfunction "NC_37") (pintype "bidirectional"))
    )
    (net (code "73") (name "unconnected-(U$1-RF_PAD-Pad36)") (class "Default")
      (node (ref "U$1") (pin "36") (pinfunction "RF_PAD_36") (pintype "bidirectional"))
    )
    (net (code "74") (name "unconnected-(U$1-VREF{slash}NC-Pad27)") (class "Default")
      (node (ref "U$1") (pin "27") (pinfunction "VREF/NC_27") (pintype "bidirectional"))
    )
    (net (code "75") (name "unconnected-(U$4-10-CS{slash}MQSR-Pad10-CS\\MQSR)") (class "Default")
      (node (ref "U$4") (pin "10-CS\\MQSR") (pinfunction "10-CS/MQSR_10-CS\\MQSR") (pintype "bidirectional"))
    )
    (net (code "76") (name "unconnected-(U$4-Pad7-RX2{slash}OUT1A)") (class "Default")
      (node (ref "U$4") (pin "7-RX2/OUT1A") (pinfunction "7-RX2/OUT1A_7-RX2/OUT1A") (pintype "bidirectional"))
    )
    (net (code "77") (name "unconnected-(U$4-Pad8-TX2{slash}IN1)") (class "Default")
      (node (ref "U$4") (pin "8-TX2/IN1") (pinfunction "8-TX2/IN1_8-TX2/IN1") (pintype "bidirectional"))
    )
    (net (code "78") (name "unconnected-(U$4-Pad9-OUT1C)") (class "Default")
      (node (ref "U$4") (pin "9-OUT1C") (pinfunction "9-OUT1C_9-OUT1C") (pintype "bidirectional"))
    )
    (net (code "79") (name "unconnected-(U$4-Pad11-MOSI{slash}CTX1)") (class "Default")
      (node (ref "U$4") (pin "11-MOSI/CTX1") (pinfunction "11-MOSI/CTX1_11-MOSI/CTX1") (pintype "bidirectional"))
    )
    (net (code "80") (name "unconnected-(U$4-Pad12-MISO{slash}MQSL)") (class "Default")
      (node (ref "U$4") (pin "12-MISO/MQSL") (pinfunction "12-MISO/MQSL_12-MISO/MQSL") (pintype "bidirectional"))
    )
    (net (code "81") (name "unconnected-(U$4-Pad13-SCK{slash}LED)") (class "Default")
      (node (ref "U$4") (pin "13-SCK/LED") (pinfunction "13-SCK/LED_13-SCK/LED") (pintype "bidirectional"))
    )
    (net (code "82") (name "unconnected-(U$4-Pad14-A0{slash}TX3{slash}SPDIF_OUT)") (class "Default")
      (node (ref "U$4") (pin "14-A0/TX3/SPDIF_OUT") (pinfunction "14-A0/TX3/SPDIF_OUT_14-A0/TX3/SPDIF_OUT") (pintype "bidirectional"))
    )
    (net (code "83") (name "unconnected-(U$4-Pad15-A1{slash}RX3{slash}SPDIF_IN)") (class "Default")
      (node (ref "U$4") (pin "15-A1/RX3/SPDIF_IN") (pinfunction "15-A1/RX3/SPDIF_IN_15-A1/RX3/SPDIF_IN") (pintype "bidirectional"))
    )
    (net (code "84") (name "unconnected-(U$4-Pad28-RX7)") (class "Default")
      (node (ref "U$4") (pin "28-RX7") (pinfunction "28-RX7_28-RX7") (pintype "bidirectional"))
    )
    (net (code "85") (name "unconnected-(U$4-Pad29-TX7)") (class "Default")
      (node (ref "U$4") (pin "29-TX7") (pinfunction "29-TX7_29-TX7") (pintype "bidirectional"))
    )
    (net (code "86") (name "unconnected-(U$4-Pad30-CRX3)") (class "Default")
      (node (ref "U$4") (pin "30-CRX3") (pinfunction "30-CRX3_30-CRX3") (pintype "bidirectional"))
    )
    (net (code "87") (name "unconnected-(U$4-Pad31-CTX3)") (class "Default")
      (node (ref "U$4") (pin "31-CTX3") (pinfunction "31-CTX3_31-CTX3") (pintype "bidirectional"))
    )
    (net (code "88") (name "unconnected-(U$4-Pad36-PWM)") (class "Default")
      (node (ref "U$4") (pin "36-PWM") (pinfunction "36-PWM_36-PWM") (pintype "bidirectional"))
    )
    (net (code "89") (name "unconnected-(U$4-Pad37-PWM)") (class "Default")
      (node (ref "U$4") (pin "37-PWM") (pinfunction "37-PWM_37-PWM") (pintype "bidirectional"))
    )
    (net (code "90") (name "unconnected-(U$4-Pad38-A14{slash}CS{slash}IN1)") (class "Default")
      (node (ref "U$4") (pin "38-A14/CS/IN1") (pinfunction "38-A14/CS/IN1_38-A14/CS/IN1") (pintype "bidirectional"))
    )
    (net (code "91") (name "unconnected-(U$4-Pad39-A15{slash}CS{slash}OUT1A)") (class "Default")
      (node (ref "U$4") (pin "39-A15/CS/OUT1A") (pinfunction "39-A15/CS/OUT1A_39-A15/CS/OUT1A") (pintype "bidirectional"))
    )
    (net (code "92") (name "unconnected-(U$4-Pad40-A16{slash}CS1)") (class "Default")
      (node (ref "U$4") (pin "40-A16/CS1") (pinfunction "40-A16/CS1_40-A16/CS1") (pintype "bidirectional"))
    )
    (net (code "93") (name "unconnected-(U$4-Pad41-A17{slash}MISO1)") (class "Default")
      (node (ref "U$4") (pin "41-A17/MISO1") (pinfunction "41-A17/MISO1_41-A17/MISO1") (pintype "bidirectional"))
    )
    (net (code "94") (name "unconnected-(U$4-PadDM)") (class "Default")
      (node (ref "U$4") (pin "DM") (pinfunction "DM_DM") (pintype "bidirectional"))
    )
    (net (code "95") (name "unconnected-(U$4-PadDP)") (class "Default")
      (node (ref "U$4") (pin "DP") (pinfunction "DP_DP") (pintype "bidirectional"))
    )
    (net (code "96") (name "unconnected-(U$4-PadON{slash}OFF)") (class "Default")
      (node (ref "U$4") (pin "ON/OFF") (pinfunction "ON/OFF_ON/OFF") (pintype "bidirectional"))
    )
    (net (code "97") (name "unconnected-(U$4-PadPROGRAM)") (class "Default")
      (node (ref "U$4") (pin "PROGRAM") (pinfunction "PROGRAM_PROGRAM") (pintype "bidirectional"))
    )
    (net (code "98") (name "unconnected-(U$4-PadVBAT)") (class "Default")
      (node (ref "U$4") (pin "VBAT") (pinfunction "VBAT_VBAT") (pintype "bidirectional"))
    )
    (net (code "99") (name "unconnected-(U$4-PadVUSB)") (class "Default")
      (node (ref "U$4") (pin "VUSB") (pinfunction "VUSB_VUSB") (pintype "bidirectional"))
    )
    (net (code "100") (name "unconnected-(U1-VREF-Pad5)") (class "Default")
      (node (ref "U1") (pin "5") (pinfunction "VREF_5") (pintype "passive"))
    )
  )
)
